# PWR_DC_DC_EXAR.net
KiCad netlist of a schematic drawn in Altium Designer
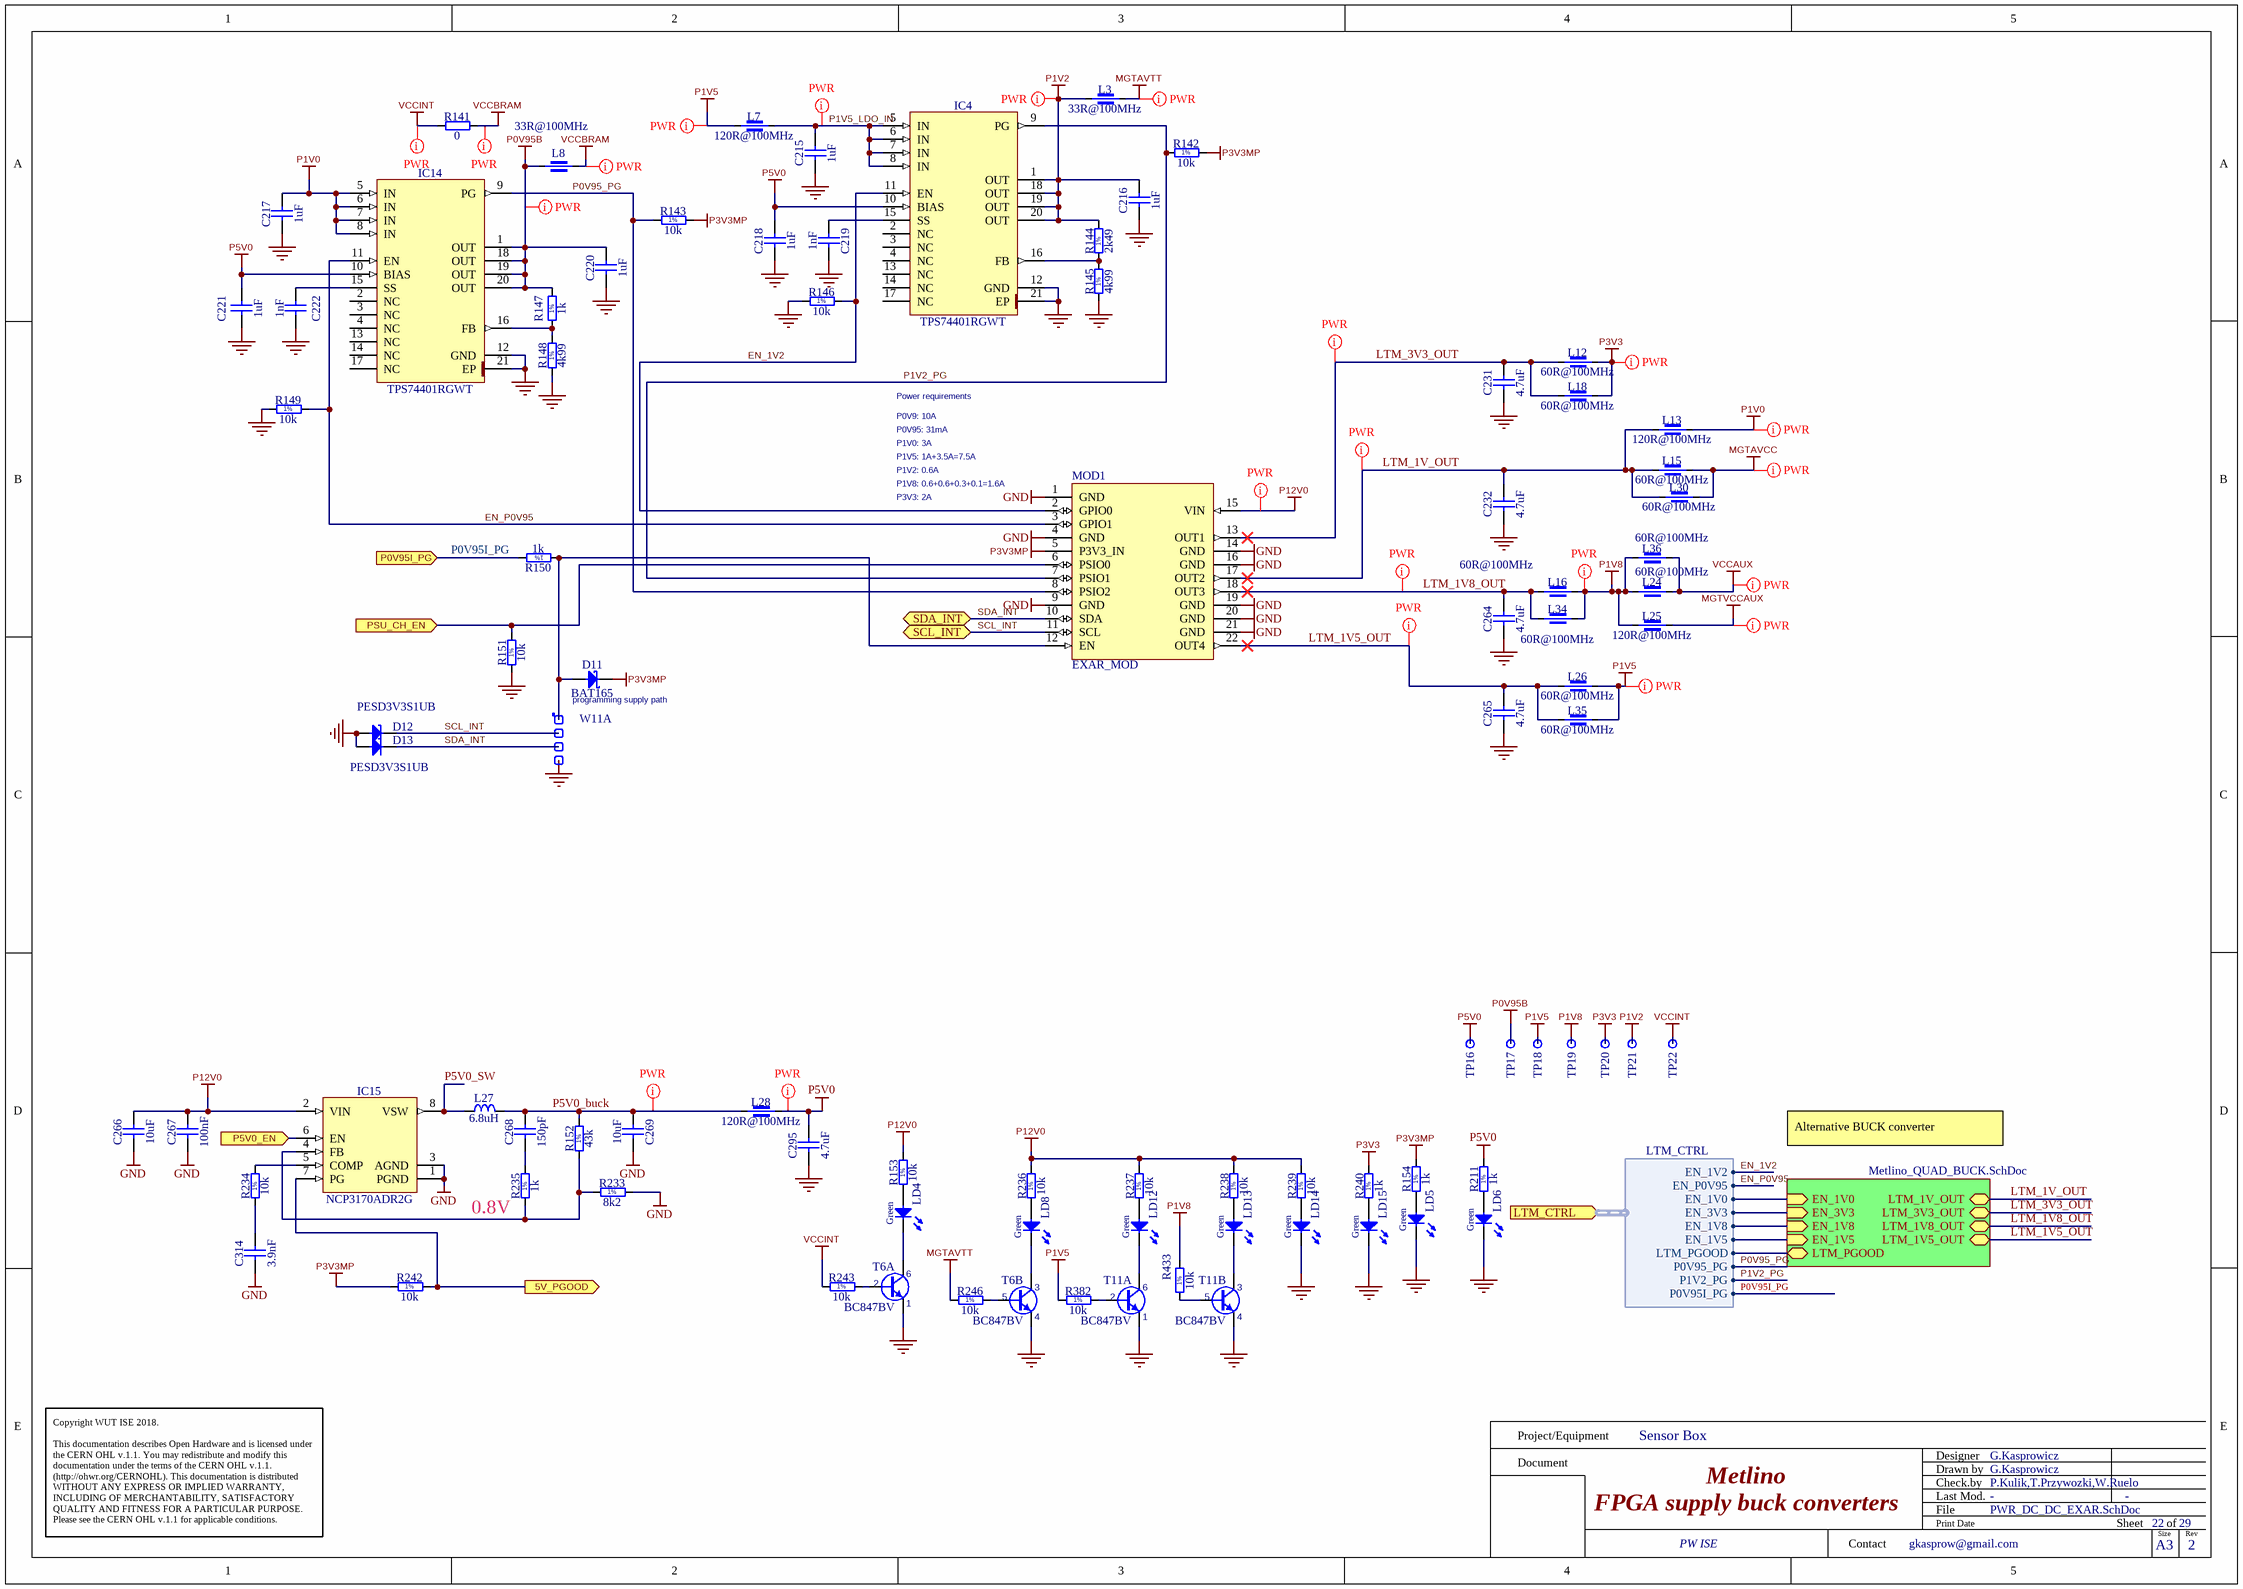
[diagram p0: PWR_DC_DC_EXAR.SchDoc]

(export (version "E")
  (design (tool "Eeschema 10.0.6"))
  (components
    (comp (ref "C215")
      (value "1uF")
      (footprint "CAPC1005X55N")
      (description "Non-polarised capacitor")
      (fields
        (field (name "MANUFACTURER PART NUMBER") "CC0402_1UF_16V_10%_X5R")
        (field (name "MANUFACTURER") "GENERIC")
        (field (name "AUTHOR") "CERN DEM JLC")
      )
      (libsource (lib "Capacitors") (part "Capacitor - non polarized"))
    )
    (comp (ref "C216")
      (value "1uF")
      (footprint "CAPC1005X55N")
      (description "Non-polarised capacitor")
      (fields
        (field (name "MANUFACTURER PART NUMBER") "CC0402_1UF_16V_10%_X5R")
        (field (name "MANUFACTURER") "GENERIC")
        (field (name "AUTHOR") "CERN DEM JLC")
      )
      (libsource (lib "Capacitors") (part "Capacitor - non polarized"))
    )
    (comp (ref "C217")
      (value "1uF")
      (footprint "CAPC1005X55N")
      (description "Non-polarised capacitor")
      (fields
        (field (name "MANUFACTURER PART NUMBER") "CC0402_1UF_16V_10%_X5R")
        (field (name "MANUFACTURER") "GENERIC")
        (field (name "AUTHOR") "CERN DEM JLC")
      )
      (libsource (lib "Capacitors") (part "Capacitor - non polarized"))
    )
    (comp (ref "C218")
      (value "1uF")
      (footprint "CAPC1005X55N")
      (description "Non-polarised capacitor")
      (fields
        (field (name "MANUFACTURER PART NUMBER") "CC0402_1UF_16V_10%_X5R")
        (field (name "MANUFACTURER") "GENERIC")
        (field (name "AUTHOR") "CERN DEM JLC")
      )
      (libsource (lib "Capacitors") (part "Capacitor - non polarized"))
    )
    (comp (ref "C219")
      (value "1nF")
      (footprint "CAPC1005X55N")
      (description "Non-polarised capacitor")
      (fields
        (field (name "MANUFACTURER PART NUMBER") "CC0402_1NF_50V_10%_X7R")
        (field (name "MANUFACTURER") "GENERIC")
        (field (name "AUTHOR") "CERN DEM JLC")
      )
      (libsource (lib "Capacitors") (part "Capacitor - non polarized"))
    )
    (comp (ref "C220")
      (value "1uF")
      (footprint "CAPC1005X55N")
      (description "Non-polarised capacitor")
      (fields
        (field (name "MANUFACTURER PART NUMBER") "CC0402_1UF_16V_10%_X5R")
        (field (name "MANUFACTURER") "GENERIC")
        (field (name "AUTHOR") "CERN DEM JLC")
      )
      (libsource (lib "Capacitors") (part "Capacitor - non polarized"))
    )
    (comp (ref "C221")
      (value "1uF")
      (footprint "CAPC1005X55N")
      (description "Non-polarised capacitor")
      (fields
        (field (name "MANUFACTURER PART NUMBER") "CC0402_1UF_16V_10%_X5R")
        (field (name "MANUFACTURER") "GENERIC")
        (field (name "AUTHOR") "CERN DEM JLC")
      )
      (libsource (lib "Capacitors") (part "Capacitor - non polarized"))
    )
    (comp (ref "C222")
      (value "1nF")
      (footprint "CAPC1005X55N")
      (description "Non-polarised capacitor")
      (fields
        (field (name "MANUFACTURER PART NUMBER") "CC0402_1NF_50V_10%_X7R")
        (field (name "MANUFACTURER") "GENERIC")
        (field (name "AUTHOR") "CERN DEM JLC")
      )
      (libsource (lib "Capacitors") (part "Capacitor - non polarized"))
    )
    (comp (ref "C231")
      (value "4.7uF")
      (footprint "CAPC1709X95N")
      (description "Non-polarised capacitor")
      (fields
        (field (name "MANUFACTURER PART NUMBER") "CC0603_4.7UF_16V_10%_X5R")
        (field (name "MANUFACTURER") "GENERIC")
        (field (name "AUTHOR") "CERN DEM JLC")
      )
      (libsource (lib "Capacitors") (part "Capacitor - non polarized"))
    )
    (comp (ref "C232")
      (value "4.7uF")
      (footprint "CAPC1709X95N")
      (description "Non-polarised capacitor")
      (fields
        (field (name "MANUFACTURER PART NUMBER") "CC0603_4.7UF_16V_10%_X5R")
        (field (name "MANUFACTURER") "GENERIC")
        (field (name "AUTHOR") "CERN DEM JLC")
      )
      (libsource (lib "Capacitors") (part "Capacitor - non polarized"))
    )
    (comp (ref "C264")
      (value "4.7uF")
      (footprint "CAPC1709X95N")
      (description "Non-polarised capacitor")
      (fields
        (field (name "MANUFACTURER PART NUMBER") "CC0603_4.7UF_16V_10%_X5R")
        (field (name "MANUFACTURER") "GENERIC")
        (field (name "AUTHOR") "CERN DEM JLC")
      )
      (libsource (lib "Capacitors") (part "Capacitor - non polarized"))
    )
    (comp (ref "C265")
      (value "4.7uF")
      (footprint "CAPC1709X95N")
      (description "Non-polarised capacitor")
      (fields
        (field (name "MANUFACTURER PART NUMBER") "CC0603_4.7UF_16V_10%_X5R")
        (field (name "MANUFACTURER") "GENERIC")
        (field (name "AUTHOR") "CERN DEM JLC")
      )
      (libsource (lib "Capacitors") (part "Capacitor - non polarized"))
    )
    (comp (ref "C266")
      (value "10uF")
      (footprint "CAPC2012X135N")
      (description "Non-polarised capacitor")
      (fields
        (field (name "PART NUMBER") "CC0805_10UF_16V_10%_X5R")
        (field (name "VOLTAGE") "16V")
        (field (name "AUTHOR") "CERN DEM JLC")
      )
      (libsource (lib "Capacitors") (part "Capacitor - non polarized"))
    )
    (comp (ref "C267")
      (value "100nF")
      (footprint "CAPC1005X55N")
      (description "Non-polarised capacitor")
      (fields
        (field (name "PART NUMBER") "CC0402_100NF_16V_10%_X5R")
        (field (name "VOLTAGE") "16V")
        (field (name "AUTHOR") "CERN DEM JLC")
      )
      (libsource (lib "Capacitors") (part "Capacitor - non polarized"))
    )
    (comp (ref "C268")
      (value "150pF")
      (footprint "CAPC1608X87N")
      (description "Non-polarised capacitor")
      (fields
        (field (name "PART NUMBER") "CC0603_150PF_50V_1%_NP0")
        (field (name "VOLTAGE") "50V")
        (field (name "AUTHOR") "CERN DEM MR")
      )
      (libsource (lib "Capacitors") (part "Capacitor - non polarized"))
    )
    (comp (ref "C269")
      (value "10uF")
      (footprint "CAPC2012X135N")
      (description "Non-polarised capacitor")
      (fields
        (field (name "PART NUMBER") "CC0805_10UF_16V_10%_X5R")
        (field (name "VOLTAGE") "16V")
        (field (name "AUTHOR") "CERN DEM JLC")
      )
      (libsource (lib "Capacitors") (part "Capacitor - non polarized"))
    )
    (comp (ref "C295")
      (value "4.7uF")
      (footprint "CAPC1709X95N")
      (description "Non-polarised capacitor")
      (fields
        (field (name "MANUFACTURER PART NUMBER") "CC0603_4.7UF_16V_10%_X5R")
        (field (name "MANUFACTURER") "GENERIC")
        (field (name "AUTHOR") "CERN DEM JLC")
      )
      (libsource (lib "Capacitors") (part "Capacitor - non polarized"))
    )
    (comp (ref "C314")
      (value "3.9nF")
      (footprint "CAPC1608X87N")
      (description "Non-polarised capacitor")
      (fields
        (field (name "PART NUMBER") "CC0603_3.9NF_50V_5%_X7R")
        (field (name "VOLTAGE") "50V")
        (field (name "AUTHOR") "CERN DEM JLC")
      )
      (libsource (lib "Capacitors") (part "Capacitor - non polarized"))
    )
    (comp (ref "D11")
      (value "BAT165")
      (footprint "SOD2512X110N")
      (description "Schottky Diode")
      (fields
        (field (name "MANUFACTURER") "INFINEON")
        (field (name "VOLTAGE") "40V")
        (field (name "AUTHOR") "CERN DEM JLC")
      )
      (libsource (lib "ICs And Semiconductors") (part "Diode Schottky"))
    )
    (comp (ref "D12")
      (value "PESD3V3S1UB")
      (footprint "SODFL1608X65N")
      (description "ESD protection diode")
      (fields
        (field (name "MANUFACTURER") "NXP SEMICONDUCTORS")
        (field (name "VOLTAGE") "3V3")
        (field (name "AUTHOR") "CERN DEM JLC")
      )
      (libsource (lib "ICs And Semiconductors") (part "Diode ESD"))
    )
    (comp (ref "D13")
      (value "PESD3V3S1UB")
      (footprint "SODFL1608X65N")
      (description "ESD protection diode")
      (fields
        (field (name "MANUFACTURER") "NXP SEMICONDUCTORS")
        (field (name "VOLTAGE") "3V3")
        (field (name "AUTHOR") "CERN DEM JLC")
      )
      (libsource (lib "ICs And Semiconductors") (part "Diode ESD"))
    )
    (comp (ref "IC4")
      (value "TPS74401RGWT")
      (footprint "QFN65P500X500X100-21N-S325")
      (description "Single Output LDO, 3.0A, Adj.(0.8 to 3.3V), Fast Transient Response, Programmable SoftStart")
      (fields (field (name "MANUFACTURER") "TEXAS INSTRUMENTS") (field (name "AUTHOR") "CERN DEM JLC"))
      (libsource (lib "ICs And Semiconductors") (part "TPS74401RGW"))
    )
    (comp (ref "IC14")
      (value "TPS74401RGWT")
      (footprint "QFN65P500X500X100-21N-S325")
      (description "Single Output LDO, 3.0A, Adj.(0.8 to 3.3V), Fast Transient Response, Programmable SoftStart")
      (fields (field (name "MANUFACTURER") "TEXAS INSTRUMENTS") (field (name "AUTHOR") "CERN DEM JLC"))
      (libsource (lib "ICs And Semiconductors") (part "TPS74401RGW"))
    )
    (comp (ref "IC15")
      (value "NCP3170ADR2G")
      (footprint "SOIC127P600X175-8N")
      (description "Synchronous PWM Switching Converter")
      (fields (field (name "MANUFACTURER") "ON SEMICONDUCTOR") (field (name "AUTHOR") "CERN DEM MR"))
      (libsource (lib "ICs And Semiconductors") (part "NCP3170ADR2G"))
    )
    (comp (ref "L3")
      (value "33R@100MHz")
      (footprint "INDC1608X95N")
      (fields
        (field (name "MANUFACTURER PART NUMBER") "BLM18PG330SN1D")
        (field (name "MANUFACTURER") "MURATA")
        (field (name "PART NUMBER") "IND0603_MURATA_BLM18PG330SN1D")
        (field (name "AUTHOR") "CERN DEM JMW")
      )
      (libsource (lib "Inductors & Transformers") (part "Ferrite Bead"))
    )
    (comp (ref "L7")
      (value "120R@100MHz")
      (footprint "INDC1608X95N")
      (fields
        (field (name "MANUFACTURER PART NUMBER") "BLM18PG121SN1D")
        (field (name "MANUFACTURER") "MURATA")
        (field (name "PART NUMBER") "IND0603_MURATA_BLM18PG121SN1D")
        (field (name "AUTHOR") "CERN DEM BC")
      )
      (libsource (lib "") (part "Ferrite Bead_1"))
    )
    (comp (ref "L8")
      (value "33R@100MHz")
      (footprint "INDC1608X95N")
      (fields
        (field (name "MANUFACTURER PART NUMBER") "BLM18PG330SN1D")
        (field (name "MANUFACTURER") "MURATA")
        (field (name "PART NUMBER") "IND0603_MURATA_BLM18PG330SN1D")
        (field (name "AUTHOR") "CERN DEM JMW")
      )
      (libsource (lib "Inductors & Transformers") (part "Ferrite Bead"))
    )
    (comp (ref "L12")
      (value "60R@100MHz")
      (footprint "INDC4516X180N")
      (fields
        (field (name "MANUFACTURER PART NUMBER") "BLM41PG600SN1L")
        (field (name "MANUFACTURER") "MURATA")
        (field (name "PART NUMBER") "IND1806_MURATA_BLM41PG600SN1L")
        (field (name "AUTHOR") "CERN DEM JLC")
      )
      (libsource (lib "Inductors & Transformers") (part "Ferrite Bead"))
    )
    (comp (ref "L13")
      (value "120R@100MHz")
      (footprint "INDC1608X95N")
      (fields
        (field (name "MANUFACTURER PART NUMBER") "BLM18PG121SN1D")
        (field (name "MANUFACTURER") "MURATA")
        (field (name "PART NUMBER") "IND0603_MURATA_BLM18PG121SN1D")
        (field (name "AUTHOR") "CERN DEM BC")
      )
      (libsource (lib "") (part "Ferrite Bead_1"))
    )
    (comp (ref "L15")
      (value "60R@100MHz")
      (footprint "INDC4516X180N")
      (fields
        (field (name "MANUFACTURER PART NUMBER") "BLM41PG600SN1L")
        (field (name "MANUFACTURER") "MURATA")
        (field (name "PART NUMBER") "IND1806_MURATA_BLM41PG600SN1L")
        (field (name "AUTHOR") "CERN DEM JLC")
      )
      (libsource (lib "Inductors & Transformers") (part "Ferrite Bead"))
    )
    (comp (ref "L16")
      (value "60R@100MHz")
      (footprint "INDC4516X180N")
      (fields
        (field (name "MANUFACTURER PART NUMBER") "BLM41PG600SN1L")
        (field (name "MANUFACTURER") "MURATA")
        (field (name "PART NUMBER") "IND1806_MURATA_BLM41PG600SN1L")
        (field (name "AUTHOR") "CERN DEM JLC")
      )
      (libsource (lib "Inductors & Transformers") (part "Ferrite Bead"))
    )
    (comp (ref "L18")
      (value "60R@100MHz")
      (footprint "INDC4516X180N")
      (fields
        (field (name "MANUFACTURER PART NUMBER") "BLM41PG600SN1L")
        (field (name "MANUFACTURER") "MURATA")
        (field (name "PART NUMBER") "IND1806_MURATA_BLM41PG600SN1L")
        (field (name "AUTHOR") "CERN DEM JLC")
      )
      (libsource (lib "Inductors & Transformers") (part "Ferrite Bead"))
    )
    (comp (ref "L24")
      (value "60R@100MHz")
      (footprint "INDC4516X180N")
      (fields
        (field (name "MANUFACTURER PART NUMBER") "BLM41PG600SN1L")
        (field (name "MANUFACTURER") "MURATA")
        (field (name "PART NUMBER") "IND1806_MURATA_BLM41PG600SN1L")
        (field (name "AUTHOR") "CERN DEM JLC")
      )
      (libsource (lib "Inductors & Transformers") (part "Ferrite Bead"))
    )
    (comp (ref "L25")
      (value "120R@100MHz")
      (footprint "INDC1608X95N")
      (fields
        (field (name "MANUFACTURER PART NUMBER") "BLM18PG121SN1D")
        (field (name "MANUFACTURER") "MURATA")
        (field (name "PART NUMBER") "IND0603_MURATA_BLM18PG121SN1D")
        (field (name "AUTHOR") "CERN DEM BC")
      )
      (libsource (lib "") (part "Ferrite Bead_1"))
    )
    (comp (ref "L26")
      (value "60R@100MHz")
      (footprint "INDC4516X180N")
      (fields
        (field (name "MANUFACTURER PART NUMBER") "BLM41PG600SN1L")
        (field (name "MANUFACTURER") "MURATA")
        (field (name "PART NUMBER") "IND1806_MURATA_BLM41PG600SN1L")
        (field (name "AUTHOR") "CERN DEM JLC")
      )
      (libsource (lib "Inductors & Transformers") (part "Ferrite Bead"))
    )
    (comp (ref "L27")
      (value "6.8uH")
      (footprint "IND_BOURNS_SRU8043")
      (description "Inductor")
      (fields
        (field (name "PART NUMBER") "IND_6.8UH_30%_BOURNS_SRU8043")
        (field (name "POWER") "3.8A")
        (field (name "AUTHOR") "CERN DEM JMW")
      )
      (libsource (lib "Inductors & Transformers") (part "Inductor"))
    )
    (comp (ref "L28")
      (value "120R@100MHz")
      (footprint "INDC1608X95N")
      (fields
        (field (name "MANUFACTURER PART NUMBER") "BLM18PG121SN1D")
        (field (name "MANUFACTURER") "MURATA")
        (field (name "PART NUMBER") "IND0603_MURATA_BLM18PG121SN1D")
        (field (name "AUTHOR") "CERN DEM BC")
      )
      (libsource (lib "") (part "Ferrite Bead_1"))
    )
    (comp (ref "L30")
      (value "60R@100MHz")
      (footprint "INDC4516X180N")
      (fields
        (field (name "MANUFACTURER PART NUMBER") "BLM41PG600SN1L")
        (field (name "MANUFACTURER") "MURATA")
        (field (name "PART NUMBER") "IND1806_MURATA_BLM41PG600SN1L")
        (field (name "AUTHOR") "CERN DEM JLC")
      )
      (libsource (lib "Inductors & Transformers") (part "Ferrite Bead"))
    )
    (comp (ref "L34")
      (value "60R@100MHz")
      (footprint "INDC4516X180N")
      (fields
        (field (name "MANUFACTURER PART NUMBER") "BLM41PG600SN1L")
        (field (name "MANUFACTURER") "MURATA")
        (field (name "PART NUMBER") "IND1806_MURATA_BLM41PG600SN1L")
        (field (name "AUTHOR") "CERN DEM JLC")
      )
      (libsource (lib "Inductors & Transformers") (part "Ferrite Bead"))
    )
    (comp (ref "L35")
      (value "60R@100MHz")
      (footprint "INDC4516X180N")
      (fields
        (field (name "MANUFACTURER PART NUMBER") "BLM41PG600SN1L")
        (field (name "MANUFACTURER") "MURATA")
        (field (name "PART NUMBER") "IND1806_MURATA_BLM41PG600SN1L")
        (field (name "AUTHOR") "CERN DEM JLC")
      )
      (libsource (lib "Inductors & Transformers") (part "Ferrite Bead"))
    )
    (comp (ref "L36")
      (value "60R@100MHz")
      (footprint "INDC4516X180N")
      (fields
        (field (name "MANUFACTURER PART NUMBER") "BLM41PG600SN1L")
        (field (name "MANUFACTURER") "MURATA")
        (field (name "PART NUMBER") "IND1806_MURATA_BLM41PG600SN1L")
        (field (name "AUTHOR") "CERN DEM JLC")
      )
      (libsource (lib "Inductors & Transformers") (part "Ferrite Bead"))
    )
    (comp (ref "LD4")
      (value "Green")
      (footprint "LED_KINGBRIGHT_KPH-1608CGCK")
      (description "LED Green 1C 2A")
      (fields
        (field (name "MANUFACTURER PART NUMBER") "KPH-1608CGCK")
        (field (name "MANUFACTURER") "KINGBRIGHT")
        (field (name "AUTHOR") "CERN DEM JLC")
      )
      (libsource (lib "ICs And Semiconductors") (part "LED Green 1C 2A"))
    )
    (comp (ref "LD5")
      (value "Green")
      (footprint "LED_KINGBRIGHT_KPH-1608CGCK")
      (description "LED Green 1C 2A")
      (fields
        (field (name "MANUFACTURER PART NUMBER") "KPH-1608CGCK")
        (field (name "MANUFACTURER") "KINGBRIGHT")
        (field (name "AUTHOR") "CERN DEM JLC")
      )
      (libsource (lib "ICs And Semiconductors") (part "LED Green 1C 2A"))
    )
    (comp (ref "LD6")
      (value "Green")
      (footprint "LED_KINGBRIGHT_KPH-1608CGCK")
      (description "LED Green 1C 2A")
      (fields
        (field (name "MANUFACTURER PART NUMBER") "KPH-1608CGCK")
        (field (name "MANUFACTURER") "KINGBRIGHT")
        (field (name "AUTHOR") "CERN DEM JLC")
      )
      (libsource (lib "ICs And Semiconductors") (part "LED Green 1C 2A"))
    )
    (comp (ref "LD8")
      (value "Green")
      (footprint "LED_KINGBRIGHT_KPH-1608CGCK")
      (description "LED Green 1C 2A")
      (fields
        (field (name "MANUFACTURER PART NUMBER") "KPH-1608CGCK")
        (field (name "MANUFACTURER") "KINGBRIGHT")
        (field (name "AUTHOR") "CERN DEM JLC")
      )
      (libsource (lib "ICs And Semiconductors") (part "LED Green 1C 2A"))
    )
    (comp (ref "LD12")
      (value "Green")
      (footprint "LED_KINGBRIGHT_KPH-1608CGCK")
      (description "LED Green 1C 2A")
      (fields
        (field (name "MANUFACTURER PART NUMBER") "KPH-1608CGCK")
        (field (name "MANUFACTURER") "KINGBRIGHT")
        (field (name "AUTHOR") "CERN DEM JLC")
      )
      (libsource (lib "ICs And Semiconductors") (part "LED Green 1C 2A"))
    )
    (comp (ref "LD13")
      (value "Green")
      (footprint "LED_KINGBRIGHT_KPH-1608CGCK")
      (description "LED Green 1C 2A")
      (fields
        (field (name "MANUFACTURER PART NUMBER") "KPH-1608CGCK")
        (field (name "MANUFACTURER") "KINGBRIGHT")
        (field (name "AUTHOR") "CERN DEM JLC")
      )
      (libsource (lib "ICs And Semiconductors") (part "LED Green 1C 2A"))
    )
    (comp (ref "LD14")
      (value "Green")
      (footprint "LED_KINGBRIGHT_KPH-1608CGCK")
      (description "LED Green 1C 2A")
      (fields
        (field (name "MANUFACTURER PART NUMBER") "KPH-1608CGCK")
        (field (name "MANUFACTURER") "KINGBRIGHT")
        (field (name "AUTHOR") "CERN DEM JLC")
      )
      (libsource (lib "ICs And Semiconductors") (part "LED Green 1C 2A"))
    )
    (comp (ref "LD15")
      (value "Green")
      (footprint "LED_KINGBRIGHT_KPH-1608CGCK")
      (description "LED Green 1C 2A")
      (fields
        (field (name "MANUFACTURER PART NUMBER") "KPH-1608CGCK")
        (field (name "MANUFACTURER") "KINGBRIGHT")
        (field (name "AUTHOR") "CERN DEM JLC")
      )
      (libsource (lib "ICs And Semiconductors") (part "LED Green 1C 2A"))
    )
    (comp (ref "MOD1")
      (value "EXAR_MOD")
      (footprint "EXAR_MOD")
      (description "4 channel PCB module based on XRP7724ILB-F")
      (libsource (lib "LIBRARY_SCH") (part "DC/DC_EXAR_MOD"))
    )
    (comp (ref "R141")
      (value "0")
      (footprint "RESC2012X60N")
      (description "Resistor")
      (fields
        (field (name "PART NUMBER") "R0805_0R_JUMPER")
        (field (name "MANUFACTURER") "GENERIC")
        (field (name "AUTHOR") "CERN DEM JLC")
      )
      (libsource (lib "Resistors") (part "Resistor"))
    )
    (comp (ref "R142")
      (value "10k")
      (footprint "RESC1005X40N")
      (description "Resistor - 1%")
      (fields
        (field (name "MANUFACTURER PART NUMBER") "R0402_10K_1%_0.0625W_100PPM")
        (field (name "MANUFACTURER") "GENERIC")
        (field (name "AUTHOR") "CERN DEM JLC")
      )
      (libsource (lib "Resistors") (part "Resistor - 1%"))
    )
    (comp (ref "R143")
      (value "10k")
      (footprint "RESC1005X40N")
      (description "Resistor - 1%")
      (fields
        (field (name "MANUFACTURER PART NUMBER") "R0402_10K_1%_0.0625W_100PPM")
        (field (name "MANUFACTURER") "GENERIC")
        (field (name "AUTHOR") "CERN DEM JLC")
      )
      (libsource (lib "Resistors") (part "Resistor - 1%"))
    )
    (comp (ref "R144")
      (value "2k49")
      (footprint "RESC1608X55N")
      (description "Resistor - 1%")
      (fields
        (field (name "MANUFACTURER PART NUMBER") "R0603_2K49_1%_0.063W_50PPM")
        (field (name "MANUFACTURER") "GENERIC")
        (field (name "AUTHOR") "CERN DEM JLC")
      )
      (libsource (lib "Resistors") (part "Resistor - 1%"))
    )
    (comp (ref "R145")
      (value "4k99")
      (footprint "RESC1608X55N")
      (description "Resistor - 1%")
      (fields
        (field (name "MANUFACTURER PART NUMBER") "R0603_4K99_1%_0.063W_50PPM")
        (field (name "MANUFACTURER") "GENERIC")
        (field (name "AUTHOR") "CERN DEM JLC")
      )
      (libsource (lib "Resistors") (part "Resistor - 1%"))
    )
    (comp (ref "R146")
      (value "10k")
      (footprint "RESC1005X40N")
      (description "Resistor - 1%")
      (fields
        (field (name "MANUFACTURER PART NUMBER") "R0402_10K_1%_0.0625W_100PPM")
        (field (name "MANUFACTURER") "GENERIC")
        (field (name "AUTHOR") "CERN DEM JLC")
      )
      (libsource (lib "Resistors") (part "Resistor - 1%"))
    )
    (comp (ref "R147")
      (value "1k")
      (footprint "RESC1005X40N")
      (description "Resistor - 1%")
      (fields
        (field (name "MANUFACTURER PART NUMBER") "R0402_1K_1%_0.0625W_100PPM")
        (field (name "MANUFACTURER") "GENERIC")
        (field (name "AUTHOR") "CERN DEM JLC")
      )
      (libsource (lib "Resistors") (part "Resistor - 1%"))
    )
    (comp (ref "R148")
      (value "4k99")
      (footprint "RESC1608X55N")
      (description "Resistor - 1%")
      (fields
        (field (name "MANUFACTURER PART NUMBER") "R0603_4K99_1%_0.063W_50PPM")
        (field (name "MANUFACTURER") "GENERIC")
        (field (name "AUTHOR") "CERN DEM JLC")
      )
      (libsource (lib "Resistors") (part "Resistor - 1%"))
    )
    (comp (ref "R149")
      (value "10k")
      (footprint "RESC1005X40N")
      (description "Resistor - 1%")
      (fields
        (field (name "MANUFACTURER PART NUMBER") "R0402_10K_1%_0.0625W_100PPM")
        (field (name "MANUFACTURER") "GENERIC")
        (field (name "AUTHOR") "CERN DEM JLC")
      )
      (libsource (lib "Resistors") (part "Resistor - 1%"))
    )
    (comp (ref "R150")
      (value "1k")
      (footprint "RESC1005X40N")
      (description "Resistor - 1%")
      (fields
        (field (name "MANUFACTURER PART NUMBER") "R0402_1K_1%_0.0625W_100PPM")
        (field (name "MANUFACTURER") "GENERIC")
        (field (name "AUTHOR") "CERN DEM JLC")
      )
      (libsource (lib "Resistors") (part "Resistor - 1%"))
    )
    (comp (ref "R151")
      (value "10k")
      (footprint "RESC1005X40N")
      (description "Resistor - 1%")
      (fields
        (field (name "MANUFACTURER PART NUMBER") "R0402_10K_1%_0.0625W_100PPM")
        (field (name "MANUFACTURER") "GENERIC")
        (field (name "AUTHOR") "CERN DEM JLC")
      )
      (libsource (lib "Resistors") (part "Resistor - 1%"))
    )
    (comp (ref "R152")
      (value "43k")
      (footprint "RESC1608X55N")
      (description "Resistor - 1%")
      (fields
        (field (name "PART NUMBER") "R0603_43K_1%_0.1W_100PPM")
        (field (name "POWER") "0.1W")
        (field (name "AUTHOR") "CERN DEM JLC")
      )
      (libsource (lib "Resistors") (part "Resistor - 1%"))
    )
    (comp (ref "R153")
      (value "10k")
      (footprint "RESC1005X40N")
      (description "Resistor - 1%")
      (fields
        (field (name "MANUFACTURER PART NUMBER") "R0402_10K_1%_0.0625W_100PPM")
        (field (name "MANUFACTURER") "GENERIC")
        (field (name "AUTHOR") "CERN DEM JLC")
      )
      (libsource (lib "Resistors") (part "Resistor - 1%"))
    )
    (comp (ref "R154")
      (value "1k")
      (footprint "RESC1005X40N")
      (description "Resistor - 1%")
      (fields
        (field (name "MANUFACTURER PART NUMBER") "R0402_1K_1%_0.0625W_100PPM")
        (field (name "MANUFACTURER") "GENERIC")
        (field (name "AUTHOR") "CERN DEM JLC")
      )
      (libsource (lib "Resistors") (part "Resistor - 1%"))
    )
    (comp (ref "R211")
      (value "1k")
      (footprint "RESC1005X40N")
      (description "Resistor - 1%")
      (fields
        (field (name "MANUFACTURER PART NUMBER") "R0402_1K_1%_0.0625W_100PPM")
        (field (name "MANUFACTURER") "GENERIC")
        (field (name "AUTHOR") "CERN DEM JLC")
      )
      (libsource (lib "Resistors") (part "Resistor - 1%"))
    )
    (comp (ref "R233")
      (value "8k2")
      (footprint "RESC1608X55N")
      (description "Resistor - 1%")
      (fields
        (field (name "PART NUMBER") "R0603_8K2_1%_0.1W_100PPM")
        (field (name "POWER") "0.1W")
        (field (name "AUTHOR") "CERN DEM JLC")
      )
      (libsource (lib "Resistors") (part "Resistor - 1%"))
    )
    (comp (ref "R234")
      (value "10k")
      (footprint "RESC1005X40N")
      (description "Resistor - 1%")
      (fields
        (field (name "PART NUMBER") "R0402_10K_1%_0.0625W_100PPM")
        (field (name "POWER") "0.0625W")
        (field (name "AUTHOR") "CERN DEM JLC")
      )
      (libsource (lib "Resistors") (part "Resistor - 1%"))
    )
    (comp (ref "R235")
      (value "1k")
      (footprint "RESC1005X40N")
      (description "Resistor - 1%")
      (fields
        (field (name "PART NUMBER") "R0402_1K_1%_0.0625W_100PPM")
        (field (name "POWER") "0.0625W")
        (field (name "AUTHOR") "CERN DEM JLC")
      )
      (libsource (lib "Resistors") (part "Resistor - 1%"))
    )
    (comp (ref "R236")
      (value "10k")
      (footprint "RESC1005X40N")
      (description "Resistor - 1%")
      (fields
        (field (name "MANUFACTURER PART NUMBER") "R0402_10K_1%_0.0625W_100PPM")
        (field (name "MANUFACTURER") "GENERIC")
        (field (name "AUTHOR") "CERN DEM JLC")
      )
      (libsource (lib "Resistors") (part "Resistor - 1%"))
    )
    (comp (ref "R237")
      (value "10k")
      (footprint "RESC1005X40N")
      (description "Resistor - 1%")
      (fields
        (field (name "MANUFACTURER PART NUMBER") "R0402_10K_1%_0.0625W_100PPM")
        (field (name "MANUFACTURER") "GENERIC")
        (field (name "AUTHOR") "CERN DEM JLC")
      )
      (libsource (lib "Resistors") (part "Resistor - 1%"))
    )
    (comp (ref "R238")
      (value "10k")
      (footprint "RESC1005X40N")
      (description "Resistor - 1%")
      (fields
        (field (name "MANUFACTURER PART NUMBER") "R0402_10K_1%_0.0625W_100PPM")
        (field (name "MANUFACTURER") "GENERIC")
        (field (name "AUTHOR") "CERN DEM JLC")
      )
      (libsource (lib "Resistors") (part "Resistor - 1%"))
    )
    (comp (ref "R239")
      (value "10k")
      (footprint "RESC1005X40N")
      (description "Resistor - 1%")
      (fields
        (field (name "MANUFACTURER PART NUMBER") "R0402_10K_1%_0.0625W_100PPM")
        (field (name "MANUFACTURER") "GENERIC")
        (field (name "AUTHOR") "CERN DEM JLC")
      )
      (libsource (lib "Resistors") (part "Resistor - 1%"))
    )
    (comp (ref "R240")
      (value "1k")
      (footprint "RESC1005X40N")
      (description "Resistor - 1%")
      (fields
        (field (name "MANUFACTURER PART NUMBER") "R0402_1K_1%_0.0625W_100PPM")
        (field (name "MANUFACTURER") "GENERIC")
        (field (name "AUTHOR") "CERN DEM JLC")
      )
      (libsource (lib "Resistors") (part "Resistor - 1%"))
    )
    (comp (ref "R242")
      (value "10k")
      (footprint "RESC1005X40N")
      (description "Resistor - 1%")
      (fields
        (field (name "MANUFACTURER PART NUMBER") "R0402_10K_1%_0.0625W_100PPM")
        (field (name "MANUFACTURER") "GENERIC")
        (field (name "AUTHOR") "CERN DEM JLC")
      )
      (libsource (lib "Resistors") (part "Resistor - 1%"))
    )
    (comp (ref "R243")
      (value "10k")
      (footprint "RESC1005X40N")
      (description "Resistor - 1%")
      (fields
        (field (name "MANUFACTURER PART NUMBER") "R0402_10K_1%_0.0625W_100PPM")
        (field (name "MANUFACTURER") "GENERIC")
        (field (name "AUTHOR") "CERN DEM JLC")
      )
      (libsource (lib "Resistors") (part "Resistor - 1%"))
    )
    (comp (ref "R246")
      (value "10k")
      (footprint "RESC1005X40N")
      (description "Resistor - 1%")
      (fields
        (field (name "MANUFACTURER PART NUMBER") "R0402_10K_1%_0.0625W_100PPM")
        (field (name "MANUFACTURER") "GENERIC")
        (field (name "AUTHOR") "CERN DEM JLC")
      )
      (libsource (lib "Resistors") (part "Resistor - 1%"))
    )
    (comp (ref "R382")
      (value "10k")
      (footprint "RESC1005X40N")
      (description "Resistor - 1%")
      (fields
        (field (name "MANUFACTURER PART NUMBER") "R0402_10K_1%_0.0625W_100PPM")
        (field (name "MANUFACTURER") "GENERIC")
        (field (name "AUTHOR") "CERN DEM JLC")
      )
      (libsource (lib "Resistors") (part "Resistor - 1%"))
    )
    (comp (ref "R433")
      (value "10k")
      (footprint "RESC1005X40N")
      (description "Resistor - 1%")
      (fields
        (field (name "MANUFACTURER PART NUMBER") "R0402_10K_1%_0.0625W_100PPM")
        (field (name "MANUFACTURER") "GENERIC")
        (field (name "AUTHOR") "CERN DEM JLC")
      )
      (libsource (lib "Resistors") (part "Resistor - 1%"))
    )
    (comp (ref "T6")
      (value "BC847BV")
      (footprint "SOTFL50P160X60-6N")
      (description "45V, 100mA NPN General Purpose Double Transistor")
      (fields (field (name "MANUFACTURER") "NXP SEMICONDUCTORS") (field (name "AUTHOR") "CERN DEM JLC"))
      (libsource (lib "ICs And Semiconductors") (part "BC847BV"))
    )
    (comp (ref "T11")
      (value "BC847BV")
      (footprint "SOTFL50P160X60-6N")
      (description "45V, 100mA NPN General Purpose Double Transistor")
      (fields (field (name "MANUFACTURER") "NXP SEMICONDUCTORS") (field (name "AUTHOR") "CERN DEM JLC"))
      (libsource (lib "ICs And Semiconductors") (part "BC847BV"))
    )
    (comp (ref "TP16")
      (value "Test Point")
      (footprint "TPS127")
      (fields (field (name "PART NUMBER") "SMD_PAD_1.27X1.27MM") (field (name "AUTHOR") "CERN DEM JLC"))
      (libsource (lib "Eletro-mechanical") (part "Test Point"))
    )
    (comp (ref "TP17")
      (value "Test Point")
      (footprint "TPS127")
      (fields (field (name "PART NUMBER") "SMD_PAD_1.27X1.27MM") (field (name "AUTHOR") "CERN DEM JLC"))
      (libsource (lib "Eletro-mechanical") (part "Test Point"))
    )
    (comp (ref "TP18")
      (value "Test Point")
      (footprint "TPS127")
      (fields (field (name "PART NUMBER") "SMD_PAD_1.27X1.27MM") (field (name "AUTHOR") "CERN DEM JLC"))
      (libsource (lib "Eletro-mechanical") (part "Test Point"))
    )
    (comp (ref "TP19")
      (value "Test Point")
      (footprint "TPS127")
      (fields (field (name "PART NUMBER") "SMD_PAD_1.27X1.27MM") (field (name "AUTHOR") "CERN DEM JLC"))
      (libsource (lib "Eletro-mechanical") (part "Test Point"))
    )
    (comp (ref "TP20")
      (value "Test Point")
      (footprint "TPS127")
      (fields (field (name "PART NUMBER") "SMD_PAD_1.27X1.27MM") (field (name "AUTHOR") "CERN DEM JLC"))
      (libsource (lib "Eletro-mechanical") (part "Test Point"))
    )
    (comp (ref "TP21")
      (value "Test Point")
      (footprint "TPS127")
      (fields (field (name "PART NUMBER") "SMD_PAD_1.27X1.27MM") (field (name "AUTHOR") "CERN DEM JLC"))
      (libsource (lib "Eletro-mechanical") (part "Test Point"))
    )
    (comp (ref "TP22")
      (value "Test Point")
      (footprint "TPS127")
      (fields (field (name "PART NUMBER") "SMD_PAD_1.27X1.27MM") (field (name "AUTHOR") "CERN DEM JLC"))
      (libsource (lib "Eletro-mechanical") (part "Test Point"))
    )
    (comp (ref "W11")
      (value "Header 4")
      (footprint "SAMTEC_MTLW-104-07-L-S-250")
      (description "4 Mini Wire-Wrap Contact Strip Header")
      (fields
        (field (name "MANUFACTURER PART NUMBER") "MTLW-104-07-L-S-250")
        (field (name "MANUFACTURER") "SAMTEC")
        (field (name "AUTHOR") "CERN DEM JLC")
      )
      (libsource (lib "Connectors") (part "Wire-Wrap Contact x4"))
    )
  )
  (nets
    (net (code "2") (name "/5V_PGOOD") (class "Default")
      (node (ref "IC15") (pin "7") (pinfunction "PG_7") (pintype "input"))
      (node (ref "R242") (pin "2") (pinfunction "2_2") (pintype "passive"))
    )
    (net (code "4") (name "/EN_1V2") (class "Default")
      (node (ref "IC4") (pin "11") (pinfunction "EN_11") (pintype "input"))
      (node (ref "MOD1") (pin "2") (pinfunction "GPIO0_2") (pintype "bidirectional"))
      (node (ref "R146") (pin "2") (pinfunction "2_2") (pintype "passive"))
    )
    (net (code "8") (name "/EN_P0V95") (class "Default")
      (node (ref "IC14") (pin "11") (pinfunction "EN_11") (pintype "input"))
      (node (ref "MOD1") (pin "3") (pinfunction "GPIO1_3") (pintype "bidirectional"))
      (node (ref "R149") (pin "2") (pinfunction "2_2") (pintype "passive"))
    )
    (net (code "9") (name "/LTM_1V5_OUT") (class "Default")
      (node (ref "C265") (pin "2") (pinfunction "2_2") (pintype "passive"))
      (node (ref "L26") (pin "1") (pinfunction "1_1") (pintype "passive"))
      (node (ref "L35") (pin "1") (pinfunction "1_1") (pintype "passive"))
      (node (ref "MOD1") (pin "22") (pinfunction "OUT4_22") (pintype "output"))
    )
    (net (code "10") (name "/LTM_1V8_OUT") (class "Default")
      (node (ref "C264") (pin "2") (pinfunction "2_2") (pintype "passive"))
      (node (ref "L16") (pin "1") (pinfunction "1_1") (pintype "passive"))
      (node (ref "L34") (pin "1") (pinfunction "1_1") (pintype "passive"))
      (node (ref "MOD1") (pin "18") (pinfunction "OUT3_18") (pintype "output"))
    )
    (net (code "11") (name "/LTM_1V_OUT") (class "Default")
      (node (ref "C232") (pin "2") (pinfunction "2_2") (pintype "passive"))
      (node (ref "L13") (pin "2") (pinfunction "2_2") (pintype "passive"))
      (node (ref "L15") (pin "1") (pinfunction "1_1") (pintype "passive"))
      (node (ref "L30") (pin "1") (pinfunction "1_1") (pintype "passive"))
      (node (ref "MOD1") (pin "17") (pinfunction "OUT2_17") (pintype "output"))
    )
    (net (code "12") (name "/LTM_3V3_OUT") (class "Default")
      (node (ref "C231") (pin "2") (pinfunction "2_2") (pintype "passive"))
      (node (ref "L12") (pin "1") (pinfunction "1_1") (pintype "passive"))
      (node (ref "L18") (pin "1") (pinfunction "1_1") (pintype "passive"))
      (node (ref "MOD1") (pin "13") (pinfunction "OUT1_13") (pintype "output"))
    )
    (net (code "14") (name "/P0V95I_PG") (class "Default")
      (node (ref "R150") (pin "2") (pinfunction "2_2") (pintype "passive"))
    )
    (net (code "15") (name "/P0V95_PG") (class "Default")
      (node (ref "IC14") (pin "9") (pinfunction "PG_9") (pintype "output"))
      (node (ref "MOD1") (pin "8") (pinfunction "PSIO2_8") (pintype "bidirectional"))
      (node (ref "R143") (pin "1") (pinfunction "1_1") (pintype "passive"))
    )
    (net (code "16") (name "/P1V2_PG") (class "Default")
      (node (ref "IC4") (pin "9") (pinfunction "PG_9") (pintype "output"))
      (node (ref "MOD1") (pin "7") (pinfunction "PSIO1_7") (pintype "bidirectional"))
      (node (ref "R142") (pin "1") (pinfunction "1_1") (pintype "passive"))
    )
    (net (code "17") (name "/P1V5_LDO_IN") (class "Default")
      (node (ref "C215") (pin "2") (pinfunction "2_2") (pintype "passive"))
      (node (ref "IC4") (pin "5") (pinfunction "IN_5") (pintype "input"))
      (node (ref "IC4") (pin "6") (pinfunction "IN_6") (pintype "input"))
      (node (ref "IC4") (pin "7") (pinfunction "IN_7") (pintype "input"))
      (node (ref "IC4") (pin "8") (pinfunction "IN_8") (pintype "input"))
      (node (ref "L7") (pin "1") (pinfunction "1_1") (pintype "passive"))
    )
    (net (code "18") (name "/P5V0_EN") (class "Default")
      (node (ref "IC15") (pin "6") (pinfunction "EN_6") (pintype "input"))
    )
    (net (code "19") (name "/P5V0_SW") (class "Default")
      (node (ref "IC15") (pin "8") (pinfunction "VSW_8") (pintype "output"))
      (node (ref "L27") (pin "1") (pinfunction "1_1") (pintype "passive"))
    )
    (net (code "20") (name "/P5V0_buck") (class "Default")
      (node (ref "C268") (pin "2") (pinfunction "2_2") (pintype "passive"))
      (node (ref "C269") (pin "1") (pinfunction "1_1") (pintype "passive"))
      (node (ref "L27") (pin "2") (pinfunction "2_2") (pintype "passive"))
      (node (ref "L28") (pin "2") (pinfunction "2_2") (pintype "passive"))
      (node (ref "R152") (pin "2") (pinfunction "2_2") (pintype "passive"))
    )
    (net (code "21") (name "/PSU_CH_EN") (class "Default")
      (node (ref "MOD1") (pin "6") (pinfunction "PSIO0_6") (pintype "bidirectional"))
      (node (ref "R151") (pin "2") (pinfunction "2_2") (pintype "passive"))
    )
    (net (code "22") (name "/SCL_INT") (class "Default")
      (node (ref "D12") (pin "1") (pinfunction "C_1") (pintype "passive"))
      (node (ref "MOD1") (pin "11") (pinfunction "SCL_11") (pintype "bidirectional"))
      (node (ref "W11") (pin "2") (pinfunction "2_2") (pintype "bidirectional"))
    )
    (net (code "23") (name "/SDA_INT") (class "Default")
      (node (ref "D13") (pin "1") (pinfunction "C_1") (pintype "passive"))
      (node (ref "MOD1") (pin "10") (pinfunction "SDA_10") (pintype "bidirectional"))
      (node (ref "W11") (pin "3") (pinfunction "3_3") (pintype "bidirectional"))
    )
    (net (code "25") (name "GND") (class "Default")
      (node (ref "C215") (pin "1") (pinfunction "1_1") (pintype "passive"))
      (node (ref "C216") (pin "1") (pinfunction "1_1") (pintype "passive"))
      (node (ref "C217") (pin "1") (pinfunction "1_1") (pintype "passive"))
      (node (ref "C218") (pin "1") (pinfunction "1_1") (pintype "passive"))
      (node (ref "C219") (pin "2") (pinfunction "2_2") (pintype "passive"))
      (node (ref "C220") (pin "1") (pinfunction "1_1") (pintype "passive"))
      (node (ref "C221") (pin "1") (pinfunction "1_1") (pintype "passive"))
      (node (ref "C222") (pin "2") (pinfunction "2_2") (pintype "passive"))
      (node (ref "C231") (pin "1") (pinfunction "1_1") (pintype "passive"))
      (node (ref "C232") (pin "1") (pinfunction "1_1") (pintype "passive"))
      (node (ref "C264") (pin "1") (pinfunction "1_1") (pintype "passive"))
      (node (ref "C265") (pin "1") (pinfunction "1_1") (pintype "passive"))
      (node (ref "C266") (pin "1") (pinfunction "1_1") (pintype "passive"))
      (node (ref "C267") (pin "1") (pinfunction "1_1") (pintype "passive"))
      (node (ref "C269") (pin "2") (pinfunction "2_2") (pintype "passive"))
      (node (ref "C295") (pin "1") (pinfunction "1_1") (pintype "passive"))
      (node (ref "C314") (pin "1") (pinfunction "1_1") (pintype "passive"))
      (node (ref "D12") (pin "2") (pinfunction "A_2") (pintype "passive"))
      (node (ref "D13") (pin "2") (pinfunction "A_2") (pintype "passive"))
      (node (ref "IC14") (pin "12") (pinfunction "GND_12") (pintype "power_in"))
      (node (ref "IC14") (pin "21") (pinfunction "EP_21") (pintype "power_in"))
      (node (ref "IC15") (pin "1") (pinfunction "PGND_1") (pintype "power_in"))
      (node (ref "IC15") (pin "3") (pinfunction "AGND_3") (pintype "power_in"))
      (node (ref "IC4") (pin "12") (pinfunction "GND_12") (pintype "power_in"))
      (node (ref "IC4") (pin "21") (pinfunction "EP_21") (pintype "power_in"))
      (node (ref "LD14") (pin "1") (pinfunction "C_1") (pintype "passive"))
      (node (ref "LD15") (pin "1") (pinfunction "C_1") (pintype "passive"))
      (node (ref "LD5") (pin "1") (pinfunction "C_1") (pintype "passive"))
      (node (ref "LD6") (pin "1") (pinfunction "C_1") (pintype "passive"))
      (node (ref "MOD1") (pin "1") (pinfunction "GND_1") (pintype "power_in"))
      (node (ref "MOD1") (pin "14") (pinfunction "GND_14") (pintype "power_in"))
      (node (ref "MOD1") (pin "16") (pinfunction "GND_16") (pintype "power_in"))
      (node (ref "MOD1") (pin "19") (pinfunction "GND_19") (pintype "power_in"))
      (node (ref "MOD1") (pin "20") (pinfunction "GND_20") (pintype "power_in"))
      (node (ref "MOD1") (pin "21") (pinfunction "GND_21") (pintype "power_in"))
      (node (ref "MOD1") (pin "4") (pinfunction "GND_4") (pintype "power_in"))
      (node (ref "MOD1") (pin "9") (pinfunction "GND_9") (pintype "power_in"))
      (node (ref "R145") (pin "1") (pinfunction "1_1") (pintype "passive"))
      (node (ref "R146") (pin "1") (pinfunction "1_1") (pintype "passive"))
      (node (ref "R148") (pin "1") (pinfunction "1_1") (pintype "passive"))
      (node (ref "R149") (pin "1") (pinfunction "1_1") (pintype "passive"))
      (node (ref "R151") (pin "1") (pinfunction "1_1") (pintype "passive"))
      (node (ref "R233") (pin "2") (pinfunction "2_2") (pintype "passive"))
      (node (ref "T11") (pin "1") (pinfunction "E_1") (pintype "passive"))
      (node (ref "T11") (pin "4") (pinfunction "E_4") (pintype "passive"))
      (node (ref "T6") (pin "1") (pinfunction "E_1") (pintype "passive"))
      (node (ref "T6") (pin "4") (pinfunction "E_4") (pintype "passive"))
      (node (ref "W11") (pin "4") (pinfunction "4_4") (pintype "bidirectional"))
    )
    (net (code "26") (name "MGTAVCC") (class "Default")
      (node (ref "L15") (pin "2") (pinfunction "2_2") (pintype "passive"))
      (node (ref "L30") (pin "2") (pinfunction "2_2") (pintype "passive"))
    )
    (net (code "27") (name "MGTAVTT") (class "Default")
      (node (ref "L3") (pin "2") (pinfunction "2_2") (pintype "passive"))
      (node (ref "R246") (pin "1") (pinfunction "1_1") (pintype "passive"))
    )
    (net (code "28") (name "MGTVCCAUX") (class "Default")
      (node (ref "L25") (pin "1") (pinfunction "1_1") (pintype "passive"))
    )
    (net (code "29") (name "Net-(C268-Pad1)") (class "Default")
      (node (ref "C268") (pin "1") (pinfunction "1_1") (pintype "passive"))
      (node (ref "R235") (pin "2") (pinfunction "2_2") (pintype "passive"))
    )
    (net (code "30") (name "Net-(C314-Pad2)") (class "Default")
      (node (ref "C314") (pin "2") (pinfunction "2_2") (pintype "passive"))
      (node (ref "R234") (pin "1") (pinfunction "1_1") (pintype "passive"))
    )
    (net (code "31") (name "Net-(D11-A)") (class "Default")
      (node (ref "D11") (pin "2") (pinfunction "A_2") (pintype "passive"))
      (node (ref "MOD1") (pin "12") (pinfunction "EN_12") (pintype "input"))
      (node (ref "R150") (pin "1") (pinfunction "1_1") (pintype "passive"))
      (node (ref "W11") (pin "1") (pinfunction "1_1") (pintype "bidirectional"))
    )
    (net (code "32") (name "Net-(IC4-FB)") (class "Default")
      (node (ref "IC4") (pin "16") (pinfunction "FB_16") (pintype "output"))
      (node (ref "R144") (pin "1") (pinfunction "1_1") (pintype "passive"))
      (node (ref "R145") (pin "2") (pinfunction "2_2") (pintype "passive"))
    )
    (net (code "33") (name "Net-(IC4-SS)") (class "Default")
      (node (ref "C219") (pin "1") (pinfunction "1_1") (pintype "passive"))
      (node (ref "IC4") (pin "15") (pinfunction "SS_15") (pintype "passive"))
    )
    (net (code "34") (name "Net-(IC14-FB)") (class "Default")
      (node (ref "IC14") (pin "16") (pinfunction "FB_16") (pintype "output"))
      (node (ref "R147") (pin "1") (pinfunction "1_1") (pintype "passive"))
      (node (ref "R148") (pin "2") (pinfunction "2_2") (pintype "passive"))
    )
    (net (code "35") (name "Net-(IC14-SS)") (class "Default")
      (node (ref "C222") (pin "1") (pinfunction "1_1") (pintype "passive"))
      (node (ref "IC14") (pin "15") (pinfunction "SS_15") (pintype "passive"))
    )
    (net (code "36") (name "Net-(IC15-COMP)") (class "Default")
      (node (ref "IC15") (pin "5") (pinfunction "COMP_5") (pintype "input"))
      (node (ref "R234") (pin "2") (pinfunction "2_2") (pintype "passive"))
    )
    (net (code "37") (name "Net-(IC15-FB)") (class "Default")
      (node (ref "IC15") (pin "4") (pinfunction "FB_4") (pintype "input"))
      (node (ref "R152") (pin "1") (pinfunction "1_1") (pintype "passive"))
      (node (ref "R233") (pin "1") (pinfunction "1_1") (pintype "passive"))
      (node (ref "R235") (pin "1") (pinfunction "1_1") (pintype "passive"))
    )
    (net (code "38") (name "Net-(LD4-A)") (class "Default")
      (node (ref "LD4") (pin "2") (pinfunction "A_2") (pintype "passive"))
      (node (ref "R153") (pin "1") (pinfunction "1_1") (pintype "passive"))
    )
    (net (code "39") (name "Net-(LD4-C)") (class "Default")
      (node (ref "LD4") (pin "1") (pinfunction "C_1") (pintype "passive"))
      (node (ref "T6") (pin "6") (pinfunction "C_6") (pintype "passive"))
    )
    (net (code "40") (name "Net-(LD5-A)") (class "Default")
      (node (ref "LD5") (pin "2") (pinfunction "A_2") (pintype "passive"))
      (node (ref "R154") (pin "1") (pinfunction "1_1") (pintype "passive"))
    )
    (net (code "41") (name "Net-(LD6-A)") (class "Default")
      (node (ref "LD6") (pin "2") (pinfunction "A_2") (pintype "passive"))
      (node (ref "R211") (pin "1") (pinfunction "1_1") (pintype "passive"))
    )
    (net (code "42") (name "Net-(LD8-A)") (class "Default")
      (node (ref "LD8") (pin "2") (pinfunction "A_2") (pintype "passive"))
      (node (ref "R236") (pin "1") (pinfunction "1_1") (pintype "passive"))
    )
    (net (code "43") (name "Net-(LD8-C)") (class "Default")
      (node (ref "LD8") (pin "1") (pinfunction "C_1") (pintype "passive"))
      (node (ref "T6") (pin "3") (pinfunction "C_3") (pintype "passive"))
    )
    (net (code "44") (name "Net-(LD12-A)") (class "Default")
      (node (ref "LD12") (pin "2") (pinfunction "A_2") (pintype "passive"))
      (node (ref "R237") (pin "1") (pinfunction "1_1") (pintype "passive"))
    )
    (net (code "45") (name "Net-(LD12-C)") (class "Default")
      (node (ref "LD12") (pin "1") (pinfunction "C_1") (pintype "passive"))
      (node (ref "T11") (pin "6") (pinfunction "C_6") (pintype "passive"))
    )
    (net (code "46") (name "Net-(LD13-A)") (class "Default")
      (node (ref "LD13") (pin "2") (pinfunction "A_2") (pintype "passive"))
      (node (ref "R238") (pin "1") (pinfunction "1_1") (pintype "passive"))
    )
    (net (code "47") (name "Net-(LD13-C)") (class "Default")
      (node (ref "LD13") (pin "1") (pinfunction "C_1") (pintype "passive"))
      (node (ref "T11") (pin "3") (pinfunction "C_3") (pintype "passive"))
    )
    (net (code "48") (name "Net-(LD14-A)") (class "Default")
      (node (ref "LD14") (pin "2") (pinfunction "A_2") (pintype "passive"))
      (node (ref "R239") (pin "1") (pinfunction "1_1") (pintype "passive"))
    )
    (net (code "49") (name "Net-(LD15-A)") (class "Default")
      (node (ref "LD15") (pin "2") (pinfunction "A_2") (pintype "passive"))
      (node (ref "R240") (pin "1") (pinfunction "1_1") (pintype "passive"))
    )
    (net (code "50") (name "Net-(T6A-B)") (class "Default")
      (node (ref "R243") (pin "2") (pinfunction "2_2") (pintype "passive"))
      (node (ref "T6") (pin "2") (pinfunction "B_2") (pintype "passive"))
    )
    (net (code "51") (name "Net-(T6B-B)") (class "Default")
      (node (ref "R246") (pin "2") (pinfunction "2_2") (pintype "passive"))
      (node (ref "T6") (pin "5") (pinfunction "B_5") (pintype "passive"))
    )
    (net (code "52") (name "Net-(T11A-B)") (class "Default")
      (node (ref "R382") (pin "2") (pinfunction "2_2") (pintype "passive"))
      (node (ref "T11") (pin "2") (pinfunction "B_2") (pintype "passive"))
    )
    (net (code "53") (name "Net-(T11B-B)") (class "Default")
      (node (ref "R433") (pin "1") (pinfunction "1_1") (pintype "passive"))
      (node (ref "T11") (pin "5") (pinfunction "B_5") (pintype "passive"))
    )
    (net (code "54") (name "P0V95B") (class "Default")
      (node (ref "C220") (pin "2") (pinfunction "2_2") (pintype "passive"))
      (node (ref "IC14") (pin "1") (pinfunction "OUT_1") (pintype "power_in"))
      (node (ref "IC14") (pin "18") (pinfunction "OUT_18") (pintype "power_in"))
      (node (ref "IC14") (pin "19") (pinfunction "OUT_19") (pintype "power_in"))
      (node (ref "IC14") (pin "20") (pinfunction "OUT_20") (pintype "power_in"))
      (node (ref "L8") (pin "1") (pinfunction "1_1") (pintype "passive"))
      (node (ref "R147") (pin "2") (pinfunction "2_2") (pintype "passive"))
      (node (ref "TP17") (pin "1") (pinfunction "1_1") (pintype "bidirectional"))
    )
    (net (code "55") (name "P1V0") (class "Default")
      (node (ref "C217") (pin "2") (pinfunction "2_2") (pintype "passive"))
      (node (ref "IC14") (pin "5") (pinfunction "IN_5") (pintype "input"))
      (node (ref "IC14") (pin "6") (pinfunction "IN_6") (pintype "input"))
      (node (ref "IC14") (pin "7") (pinfunction "IN_7") (pintype "input"))
      (node (ref "IC14") (pin "8") (pinfunction "IN_8") (pintype "input"))
      (node (ref "L13") (pin "1") (pinfunction "1_1") (pintype "passive"))
    )
    (net (code "56") (name "P1V2") (class "Default")
      (node (ref "C216") (pin "2") (pinfunction "2_2") (pintype "passive"))
      (node (ref "IC4") (pin "1") (pinfunction "OUT_1") (pintype "power_in"))
      (node (ref "IC4") (pin "18") (pinfunction "OUT_18") (pintype "power_in"))
      (node (ref "IC4") (pin "19") (pinfunction "OUT_19") (pintype "power_in"))
      (node (ref "IC4") (pin "20") (pinfunction "OUT_20") (pintype "power_in"))
      (node (ref "L3") (pin "1") (pinfunction "1_1") (pintype "passive"))
      (node (ref "R144") (pin "2") (pinfunction "2_2") (pintype "passive"))
      (node (ref "TP21") (pin "1") (pinfunction "1_1") (pintype "bidirectional"))
    )
    (net (code "57") (name "P1V5") (class "Default")
      (node (ref "L26") (pin "2") (pinfunction "2_2") (pintype "passive"))
      (node (ref "L35") (pin "2") (pinfunction "2_2") (pintype "passive"))
      (node (ref "L7") (pin "2") (pinfunction "2_2") (pintype "passive"))
      (node (ref "R382") (pin "1") (pinfunction "1_1") (pintype "passive"))
      (node (ref "TP18") (pin "1") (pinfunction "1_1") (pintype "bidirectional"))
    )
    (net (code "58") (name "P1V8") (class "Default")
      (node (ref "L16") (pin "2") (pinfunction "2_2") (pintype "passive"))
      (node (ref "L24") (pin "1") (pinfunction "1_1") (pintype "passive"))
      (node (ref "L25") (pin "2") (pinfunction "2_2") (pintype "passive"))
      (node (ref "L34") (pin "2") (pinfunction "2_2") (pintype "passive"))
      (node (ref "L36") (pin "1") (pinfunction "1_1") (pintype "passive"))
      (node (ref "R433") (pin "2") (pinfunction "2_2") (pintype "passive"))
      (node (ref "TP19") (pin "1") (pinfunction "1_1") (pintype "bidirectional"))
    )
    (net (code "59") (name "P3V3") (class "Default")
      (node (ref "L12") (pin "2") (pinfunction "2_2") (pintype "passive"))
      (node (ref "L18") (pin "2") (pinfunction "2_2") (pintype "passive"))
      (node (ref "R240") (pin "2") (pinfunction "2_2") (pintype "passive"))
      (node (ref "TP20") (pin "1") (pinfunction "1_1") (pintype "bidirectional"))
    )
    (net (code "60") (name "P3V3MP") (class "Default")
      (node (ref "D11") (pin "1") (pinfunction "C_1") (pintype "passive"))
      (node (ref "MOD1") (pin "5") (pinfunction "P3V3_IN_5") (pintype "power_in"))
      (node (ref "R142") (pin "2") (pinfunction "2_2") (pintype "passive"))
      (node (ref "R143") (pin "2") (pinfunction "2_2") (pintype "passive"))
      (node (ref "R154") (pin "2") (pinfunction "2_2") (pintype "passive"))
      (node (ref "R242") (pin "1") (pinfunction "1_1") (pintype "passive"))
    )
    (net (code "61") (name "P5V0") (class "Default")
      (node (ref "C218") (pin "2") (pinfunction "2_2") (pintype "passive"))
      (node (ref "C221") (pin "2") (pinfunction "2_2") (pintype "passive"))
      (node (ref "C295") (pin "2") (pinfunction "2_2") (pintype "passive"))
      (node (ref "IC14") (pin "10") (pinfunction "BIAS_10") (pintype "input"))
      (node (ref "IC4") (pin "10") (pinfunction "BIAS_10") (pintype "input"))
      (node (ref "L28") (pin "1") (pinfunction "1_1") (pintype "passive"))
      (node (ref "R211") (pin "2") (pinfunction "2_2") (pintype "passive"))
      (node (ref "TP16") (pin "1") (pinfunction "1_1") (pintype "bidirectional"))
    )
    (net (code "62") (name "P12V0") (class "Default")
      (node (ref "C266") (pin "2") (pinfunction "2_2") (pintype "passive"))
      (node (ref "C267") (pin "2") (pinfunction "2_2") (pintype "passive"))
      (node (ref "IC15") (pin "2") (pinfunction "VIN_2") (pintype "input"))
      (node (ref "MOD1") (pin "15") (pinfunction "VIN_15") (pintype "input"))
      (node (ref "R153") (pin "2") (pinfunction "2_2") (pintype "passive"))
      (node (ref "R236") (pin "2") (pinfunction "2_2") (pintype "passive"))
      (node (ref "R237") (pin "2") (pinfunction "2_2") (pintype "passive"))
      (node (ref "R238") (pin "2") (pinfunction "2_2") (pintype "passive"))
      (node (ref "R239") (pin "2") (pinfunction "2_2") (pintype "passive"))
    )
    (net (code "63") (name "VCCAUX") (class "Default")
      (node (ref "L24") (pin "2") (pinfunction "2_2") (pintype "passive"))
      (node (ref "L36") (pin "2") (pinfunction "2_2") (pintype "passive"))
    )
    (net (code "64") (name "VCCBRAM") (class "Default")
      (node (ref "L8") (pin "2") (pinfunction "2_2") (pintype "passive"))
      (node (ref "R141") (pin "2") (pinfunction "2_2") (pintype "passive"))
    )
    (net (code "65") (name "VCCINT") (class "Default")
      (node (ref "R141") (pin "1") (pinfunction "1_1") (pintype "passive"))
      (node (ref "R243") (pin "1") (pinfunction "1_1") (pintype "passive"))
      (node (ref "TP22") (pin "1") (pinfunction "1_1") (pintype "bidirectional"))
    )
    (net (code "66") (name "unconnected-(IC4-NC-Pad2)") (class "Default")
      (node (ref "IC4") (pin "2") (pinfunction "NC_2") (pintype "passive"))
    )
    (net (code "67") (name "unconnected-(IC4-NC-Pad3)") (class "Default")
      (node (ref "IC4") (pin "3") (pinfunction "NC_3") (pintype "passive"))
    )
    (net (code "68") (name "unconnected-(IC4-NC-Pad4)") (class "Default")
      (node (ref "IC4") (pin "4") (pinfunction "NC_4") (pintype "passive"))
    )
    (net (code "69") (name "unconnected-(IC4-NC-Pad13)") (class "Default")
      (node (ref "IC4") (pin "13") (pinfunction "NC_13") (pintype "passive"))
    )
    (net (code "70") (name "unconnected-(IC4-NC-Pad14)") (class "Default")
      (node (ref "IC4") (pin "14") (pinfunction "NC_14") (pintype "passive"))
    )
    (net (code "71") (name "unconnected-(IC4-NC-Pad17)") (class "Default")
      (node (ref "IC4") (pin "17") (pinfunction "NC_17") (pintype "passive"))
    )
    (net (code "72") (name "unconnected-(IC14-NC-Pad2)") (class "Default")
      (node (ref "IC14") (pin "2") (pinfunction "NC_2") (pintype "passive"))
    )
    (net (code "73") (name "unconnected-(IC14-NC-Pad3)") (class "Default")
      (node (ref "IC14") (pin "3") (pinfunction "NC_3") (pintype "passive"))
    )
    (net (code "74") (name "unconnected-(IC14-NC-Pad4)") (class "Default")
      (node (ref "IC14") (pin "4") (pinfunction "NC_4") (pintype "passive"))
    )
    (net (code "75") (name "unconnected-(IC14-NC-Pad13)") (class "Default")
      (node (ref "IC14") (pin "13") (pinfunction "NC_13") (pintype "passive"))
    )
    (net (code "76") (name "unconnected-(IC14-NC-Pad14)") (class "Default")
      (node (ref "IC14") (pin "14") (pinfunction "NC_14") (pintype "passive"))
    )
    (net (code "77") (name "unconnected-(IC14-NC-Pad17)") (class "Default")
      (node (ref "IC14") (pin "17") (pinfunction "NC_17") (pintype "passive"))
    )
  )
)
